# MK.net
KiCad netlist of a schematic drawn in EAGLE
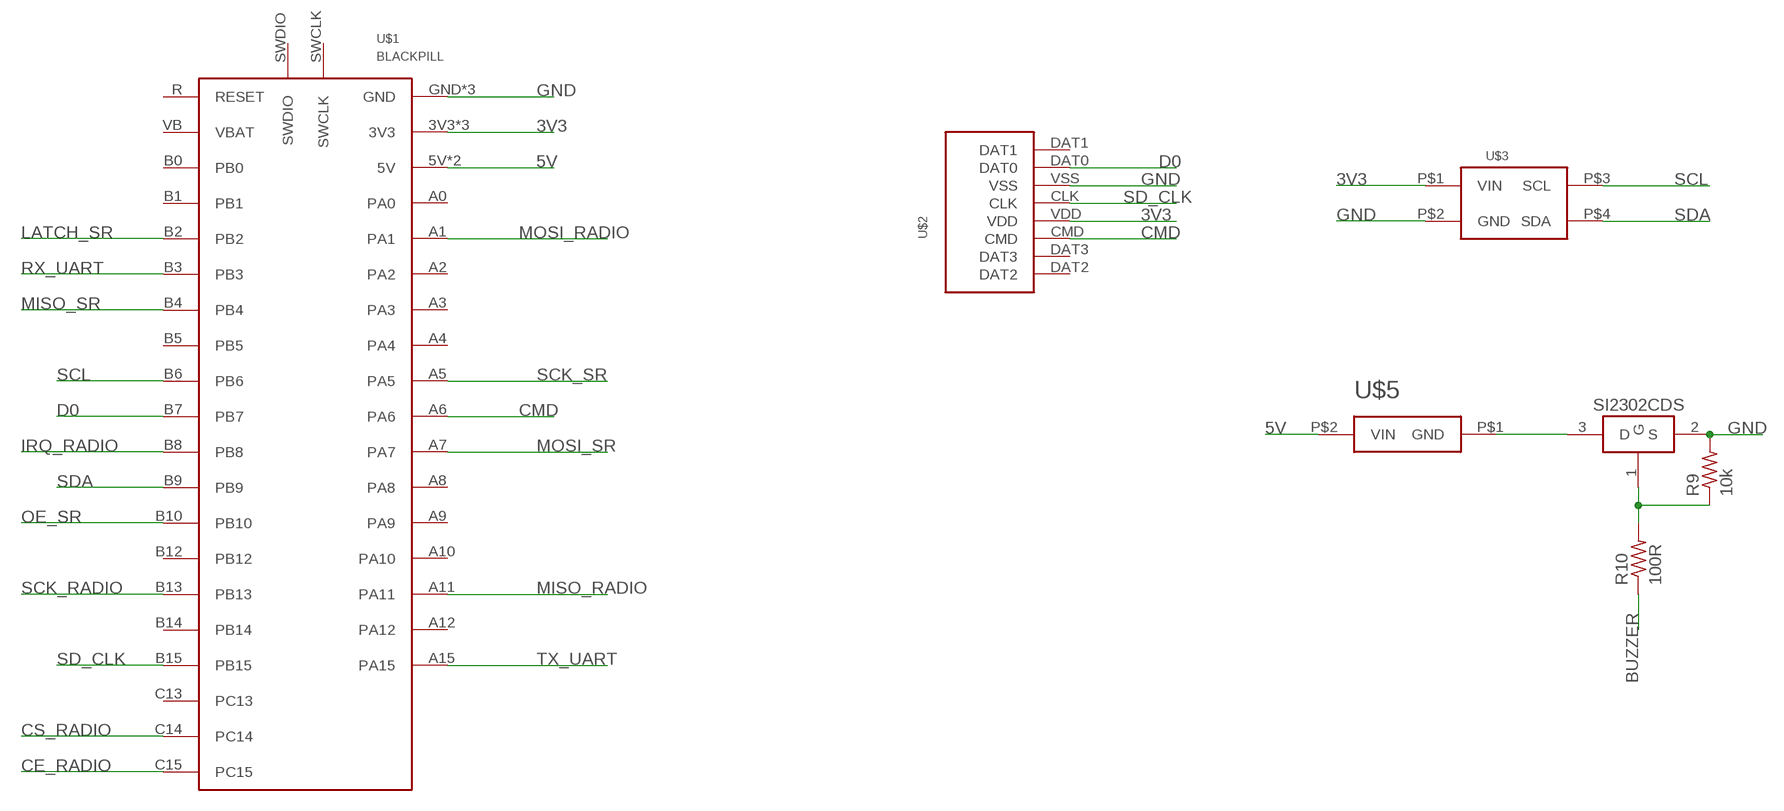
[diagram p0: schematic, sheet 1]

(export (version "E")
  (design (tool "Eeschema 10.0.6"))
  (components
    (comp (ref "R9")
      (value "10k")
      (footprint "eagle-import:R0603")
      (libsource (lib "eagle-import") (part "R-US_R0603"))
    )
    (comp (ref "R10")
      (value "100R")
      (footprint "eagle-import:R0603")
      (libsource (lib "eagle-import") (part "R-US_R0603"))
    )
    (comp (ref "U$1")
      (value "BLACKPILL")
      (footprint "eagle-import:BLACKPILL")
      (libsource (lib "eagle-import") (part "BLACKPILL"))
    )
    (comp (ref "U$2") (value "SD") (footprint "eagle-import:SD") (libsource (lib "eagle-import") (part "SD")))
    (comp (ref "U$3")
      (value "BME280")
      (footprint "eagle-import:BME280")
      (libsource (lib "eagle-import") (part "BME280"))
    )
    (comp (ref "U$5")
      (value "BUZZERS8R6")
      (footprint "eagle-import:BUZZER-S8R12")
      (libsource (lib "eagle-import") (part "BUZZERS8R6"))
    )
    (comp (ref "U$20")
      (value "SI2302CDS")
      (footprint "eagle-import:SOT23-3")
      (libsource (lib "eagle-import") (part "SI2302CDS"))
    )
  )
  (nets
    (net (code "1") (name "/3V3") (class "Default")
      (node (ref "U$1") (pin "3V3") (pinfunction "3V3_3V3") (pintype "bidirectional"))
      (node (ref "U$1") (pin "3V31") (pinfunction "3V3_3V31") (pintype "bidirectional"))
      (node (ref "U$1") (pin "3V32") (pinfunction "3V3_3V32") (pintype "bidirectional"))
      (node (ref "U$2") (pin "VDD") (pinfunction "VDD_VDD") (pintype "bidirectional"))
      (node (ref "U$3") (pin "P$1") (pinfunction "VIN_P$1") (pintype "bidirectional"))
    )
    (net (code "2") (name "/5V") (class "Default")
      (node (ref "U$1") (pin "5V") (pinfunction "5V_5V") (pintype "bidirectional"))
      (node (ref "U$1") (pin "5V1") (pinfunction "5V_5V1") (pintype "bidirectional"))
      (node (ref "U$5") (pin "P$2") (pinfunction "VIN_P$2") (pintype "bidirectional"))
    )
    (net (code "3") (name "/BUZZER") (class "Default")
      (node (ref "R10") (pin "1") (pinfunction "1_1") (pintype "passive"))
    )
    (net (code "4") (name "/CE_RADIO") (class "Default")
      (node (ref "U$1") (pin "C15") (pinfunction "PC15_C15") (pintype "bidirectional"))
    )
    (net (code "5") (name "/CMD") (class "Default")
      (node (ref "U$1") (pin "A6") (pinfunction "PA6_A6") (pintype "bidirectional"))
      (node (ref "U$2") (pin "CMD") (pinfunction "CMD_CMD") (pintype "bidirectional"))
    )
    (net (code "6") (name "/CS_RADIO") (class "Default")
      (node (ref "U$1") (pin "C14") (pinfunction "PC14_C14") (pintype "bidirectional"))
    )
    (net (code "7") (name "/D0") (class "Default")
      (node (ref "U$1") (pin "B7") (pinfunction "PB7_B7") (pintype "bidirectional"))
      (node (ref "U$2") (pin "DAT0") (pinfunction "DAT0_DAT0") (pintype "bidirectional"))
    )
    (net (code "8") (name "/GND") (class "Default")
      (node (ref "R9") (pin "2") (pinfunction "2_2") (pintype "passive"))
      (node (ref "U$1") (pin "GND") (pinfunction "GND_GND") (pintype "bidirectional"))
      (node (ref "U$1") (pin "GND1") (pinfunction "GND_GND1") (pintype "bidirectional"))
      (node (ref "U$1") (pin "GND3") (pinfunction "GND_GND3") (pintype "bidirectional"))
      (node (ref "U$2") (pin "VSS") (pinfunction "VSS_VSS") (pintype "bidirectional"))
      (node (ref "U$20") (pin "2") (pinfunction "S_2") (pintype "bidirectional"))
      (node (ref "U$3") (pin "P$2") (pinfunction "GND_P$2") (pintype "bidirectional"))
    )
    (net (code "9") (name "/IRQ_RADIO") (class "Default")
      (node (ref "U$1") (pin "B8") (pinfunction "PB8_B8") (pintype "bidirectional"))
    )
    (net (code "10") (name "/LATCH_SR") (class "Default")
      (node (ref "U$1") (pin "B2") (pinfunction "PB2_B2") (pintype "bidirectional"))
    )
    (net (code "11") (name "/MISO_RADIO") (class "Default")
      (node (ref "U$1") (pin "A11") (pinfunction "PA11_A11") (pintype "bidirectional"))
    )
    (net (code "12") (name "/MISO_SR") (class "Default")
      (node (ref "U$1") (pin "B4") (pinfunction "PB4_B4") (pintype "bidirectional"))
    )
    (net (code "13") (name "/MOSI_RADIO") (class "Default")
      (node (ref "U$1") (pin "A1") (pinfunction "PA1_A1") (pintype "bidirectional"))
    )
    (net (code "14") (name "/MOSI_SR") (class "Default")
      (node (ref "U$1") (pin "A7") (pinfunction "PA7_A7") (pintype "bidirectional"))
    )
    (net (code "15") (name "/OE_SR") (class "Default")
      (node (ref "U$1") (pin "B10") (pinfunction "PB10_B10") (pintype "bidirectional"))
    )
    (net (code "16") (name "/RX_UART") (class "Default")
      (node (ref "U$1") (pin "B3") (pinfunction "PB3_B3") (pintype "bidirectional"))
    )
    (net (code "17") (name "/SCK_RADIO") (class "Default")
      (node (ref "U$1") (pin "B13") (pinfunction "PB13_B13") (pintype "bidirectional"))
    )
    (net (code "18") (name "/SCK_SR") (class "Default")
      (node (ref "U$1") (pin "A5") (pinfunction "PA5_A5") (pintype "bidirectional"))
    )
    (net (code "19") (name "/SCL") (class "Default")
      (node (ref "U$1") (pin "B6") (pinfunction "PB6_B6") (pintype "bidirectional"))
      (node (ref "U$3") (pin "P$3") (pinfunction "SCL_P$3") (pintype "bidirectional"))
    )
    (net (code "20") (name "/SDA") (class "Default")
      (node (ref "U$1") (pin "B9") (pinfunction "PB9_B9") (pintype "bidirectional"))
      (node (ref "U$3") (pin "P$4") (pinfunction "SDA_P$4") (pintype "bidirectional"))
    )
    (net (code "21") (name "/SD_CLK") (class "Default")
      (node (ref "U$1") (pin "B15") (pinfunction "PB15_B15") (pintype "bidirectional"))
      (node (ref "U$2") (pin "CLK") (pinfunction "CLK_CLK") (pintype "bidirectional"))
    )
    (net (code "22") (name "/TX_UART") (class "Default")
      (node (ref "U$1") (pin "A15") (pinfunction "PA15_A15") (pintype "bidirectional"))
    )
    (net (code "23") (name "Net-(U$20-D)") (class "Default")
      (node (ref "U$20") (pin "3") (pinfunction "D_3") (pintype "bidirectional"))
      (node (ref "U$5") (pin "P$1") (pinfunction "GND_P$1") (pintype "bidirectional"))
    )
    (net (code "24") (name "Net-(U$20-G)") (class "Default")
      (node (ref "R10") (pin "2") (pinfunction "2_2") (pintype "passive"))
      (node (ref "R9") (pin "1") (pinfunction "1_1") (pintype "passive"))
      (node (ref "U$20") (pin "1") (pinfunction "G_1") (pintype "bidirectional"))
    )
    (net (code "25") (name "unconnected-(U$1-PA0-PadA0)") (class "Default")
      (node (ref "U$1") (pin "A0") (pinfunction "PA0_A0") (pintype "bidirectional"))
    )
    (net (code "26") (name "unconnected-(U$1-PA2-PadA2)") (class "Default")
      (node (ref "U$1") (pin "A2") (pinfunction "PA2_A2") (pintype "bidirectional"))
    )
    (net (code "27") (name "unconnected-(U$1-PA3-PadA3)") (class "Default")
      (node (ref "U$1") (pin "A3") (pinfunction "PA3_A3") (pintype "bidirectional"))
    )
    (net (code "28") (name "unconnected-(U$1-PA4-PadA4)") (class "Default")
      (node (ref "U$1") (pin "A4") (pinfunction "PA4_A4") (pintype "bidirectional"))
    )
    (net (code "29") (name "unconnected-(U$1-PA8-PadA8)") (class "Default")
      (node (ref "U$1") (pin "A8") (pinfunction "PA8_A8") (pintype "bidirectional"))
    )
    (net (code "30") (name "unconnected-(U$1-PA9-PadA9)") (class "Default")
      (node (ref "U$1") (pin "A9") (pinfunction "PA9_A9") (pintype "bidirectional"))
    )
    (net (code "31") (name "unconnected-(U$1-PA10-PadA10)") (class "Default")
      (node (ref "U$1") (pin "A10") (pinfunction "PA10_A10") (pintype "bidirectional"))
    )
    (net (code "32") (name "unconnected-(U$1-PA12-PadA12)") (class "Default")
      (node (ref "U$1") (pin "A12") (pinfunction "PA12_A12") (pintype "bidirectional"))
    )
    (net (code "33") (name "unconnected-(U$1-PB0-PadB0)") (class "Default")
      (node (ref "U$1") (pin "B0") (pinfunction "PB0_B0") (pintype "bidirectional"))
    )
    (net (code "34") (name "unconnected-(U$1-PB1-PadB1)") (class "Default")
      (node (ref "U$1") (pin "B1") (pinfunction "PB1_B1") (pintype "bidirectional"))
    )
    (net (code "35") (name "unconnected-(U$1-PB5-PadB5)") (class "Default")
      (node (ref "U$1") (pin "B5") (pinfunction "PB5_B5") (pintype "bidirectional"))
    )
    (net (code "36") (name "unconnected-(U$1-PB12-PadB12)") (class "Default")
      (node (ref "U$1") (pin "B12") (pinfunction "PB12_B12") (pintype "bidirectional"))
    )
    (net (code "37") (name "unconnected-(U$1-PB14-PadB14)") (class "Default")
      (node (ref "U$1") (pin "B14") (pinfunction "PB14_B14") (pintype "bidirectional"))
    )
    (net (code "38") (name "unconnected-(U$1-PC13-PadC13)") (class "Default")
      (node (ref "U$1") (pin "C13") (pinfunction "PC13_C13") (pintype "bidirectional"))
    )
    (net (code "39") (name "unconnected-(U$1-PadSWCLK)") (class "Default")
      (node (ref "U$1") (pin "SWCLK") (pinfunction "SWCLK_SWCLK") (pintype "bidirectional"))
    )
    (net (code "40") (name "unconnected-(U$1-PadSWDIO)") (class "Default")
      (node (ref "U$1") (pin "SWDIO") (pinfunction "SWDIO_SWDIO") (pintype "bidirectional"))
    )
    (net (code "41") (name "unconnected-(U$1-RESET-PadR)") (class "Default")
      (node (ref "U$1") (pin "R") (pinfunction "RESET_R") (pintype "bidirectional"))
    )
    (net (code "42") (name "unconnected-(U$1-VBAT-PadVB)") (class "Default")
      (node (ref "U$1") (pin "VB") (pinfunction "VBAT_VB") (pintype "bidirectional"))
    )
    (net (code "43") (name "unconnected-(U$2-PadDAT1)") (class "Default")
      (node (ref "U$2") (pin "DAT1") (pinfunction "DAT1_DAT1") (pintype "bidirectional"))
    )
    (net (code "44") (name "unconnected-(U$2-PadDAT2)") (class "Default")
      (node (ref "U$2") (pin "DAT2") (pinfunction "DAT2_DAT2") (pintype "bidirectional"))
    )
    (net (code "45") (name "unconnected-(U$2-PadDAT3)") (class "Default")
      (node (ref "U$2") (pin "DAT3") (pinfunction "DAT3_DAT3") (pintype "bidirectional"))
    )
  )
)
